# K60.net
KiCad netlist of a schematic drawn in Altium Designer
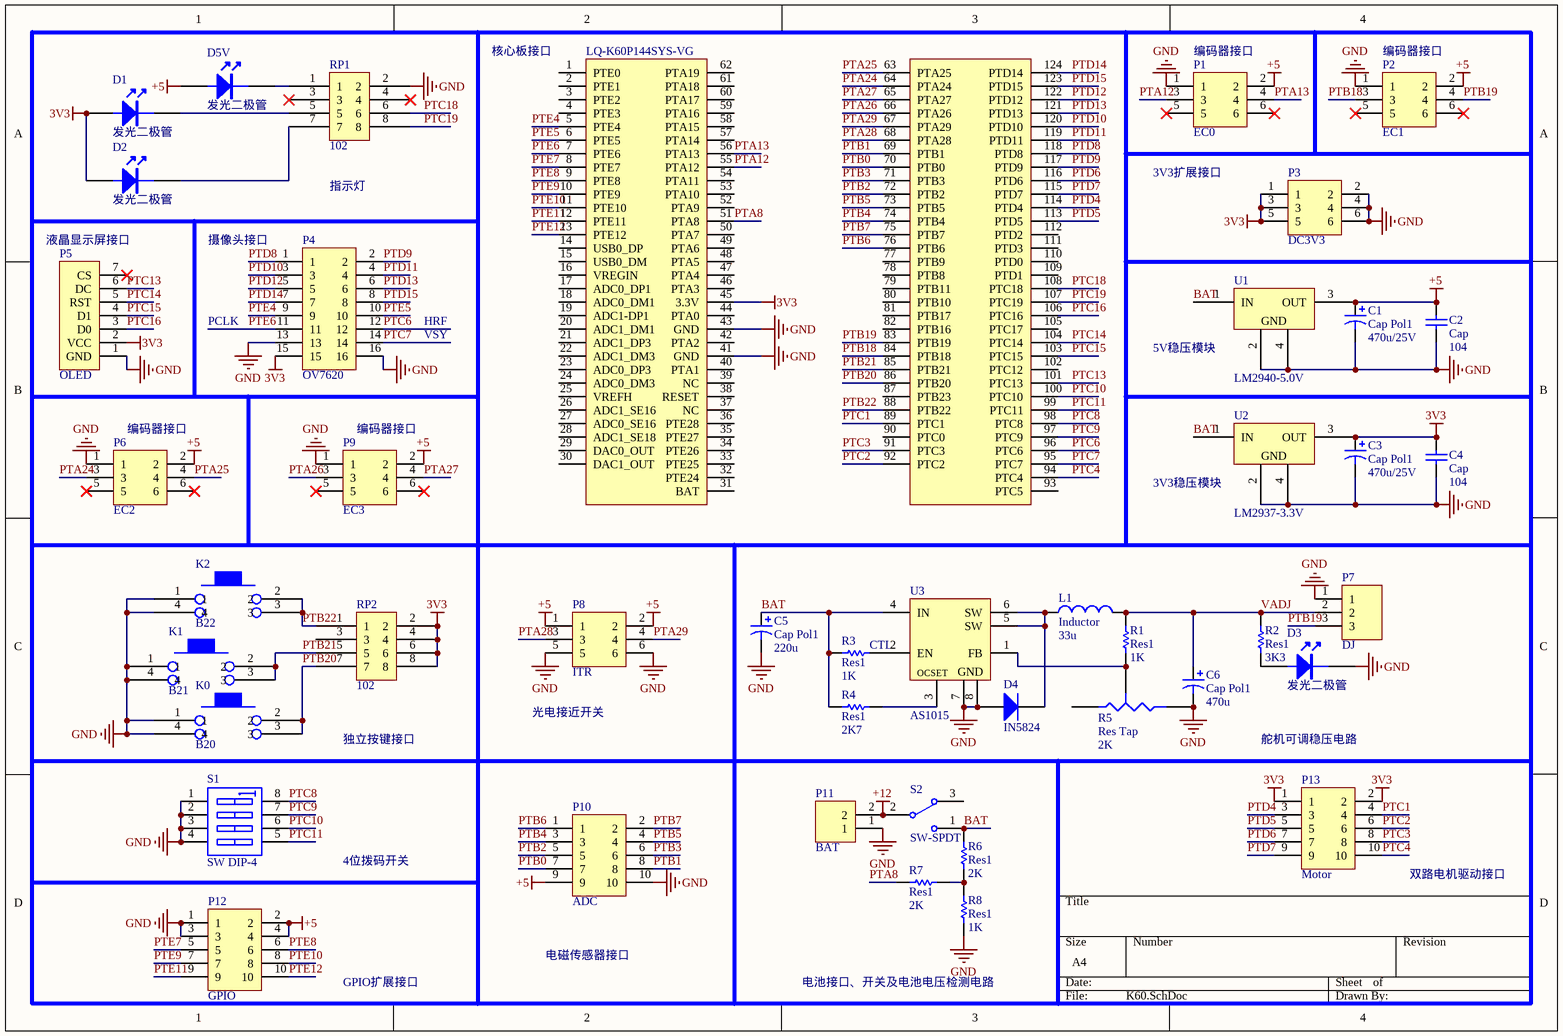
[diagram p0: K60.SchDoc]

(export (version "E")
  (design (tool "Eeschema 10.0.6"))
  (components
    (comp (ref "C1")
      (value "Cap Pol1")
      (footprint "CT 8*7 - C")
      (description "Polarized Capacitor (Radial)")
      (fields (field (name "ALTIUM_VALUE") "470u/25V") (field (name "PUBLISHER") "Altium Limited"))
      (libsource (lib "Miscellaneous Devices") (part "Cap Pol1"))
    )
    (comp (ref "C2")
      (value "Cap")
      (footprint "0603")
      (description "Capacitor")
      (fields (field (name "ALTIUM_VALUE") "104") (field (name "PUBLISHER") "Altium Limited"))
      (libsource (lib "Miscellaneous Devices") (part "Cap"))
    )
    (comp (ref "C3")
      (value "Cap Pol1")
      (footprint "CT 8*7 - C")
      (description "Polarized Capacitor (Radial)")
      (fields (field (name "ALTIUM_VALUE") "470u/25V") (field (name "PUBLISHER") "Altium Limited"))
      (libsource (lib "Miscellaneous Devices") (part "Cap Pol1"))
    )
    (comp (ref "C4")
      (value "Cap")
      (footprint "0603")
      (description "Capacitor")
      (fields (field (name "ALTIUM_VALUE") "104") (field (name "PUBLISHER") "Altium Limited"))
      (libsource (lib "Miscellaneous Devices") (part "Cap"))
    )
    (comp (ref "C5")
      (value "Cap Pol1")
      (footprint "CT 8*7 - C")
      (description "Polarized Capacitor (Radial)")
      (fields (field (name "ALTIUM_VALUE") "220u") (field (name "PUBLISHER") "Altium Limited"))
      (libsource (lib "Miscellaneous Devices") (part "Cap Pol1"))
    )
    (comp (ref "C6")
      (value "Cap Pol1")
      (footprint "CT 8*7 - C")
      (description "Polarized Capacitor (Radial)")
      (fields (field (name "ALTIUM_VALUE") "470u") (field (name "PUBLISHER") "Altium Limited"))
      (libsource (lib "Miscellaneous Devices") (part "Cap Pol1"))
    )
    (comp (ref "D1") (value "发光二极管") (footprint "0603") (libsource (lib "K60") (part "发光二极管")))
    (comp (ref "D2") (value "发光二极管") (footprint "0603") (libsource (lib "K60") (part "发光二极管")))
    (comp (ref "D3") (value "发光二极管") (footprint "0603") (libsource (lib "K60") (part "发光二极管")))
    (comp (ref "D4")
      (value "IN5824")
      (footprint "SMA")
      (description "SS54")
      (fields (field (name "PUBLISHER") "Altium Limited"))
      (libsource (lib "Miscellaneous Devices") (part "Diode"))
    )
    (comp (ref "D5V") (value "发光二极管") (footprint "0603") (libsource (lib "K60") (part "发光二极管")))
    (comp (ref "K0")
      (value "B20")
      (footprint "TSW DIP-6*6*6")
      (libsource (lib "LQ_KXXP144-SYSVGSCH") (part "key"))
    )
    (comp (ref "K1")
      (value "B21")
      (footprint "TSW DIP-6*6*6")
      (libsource (lib "LQ_KXXP144-SYSVGSCH") (part "key"))
    )
    (comp (ref "K2")
      (value "B22")
      (footprint "TSW DIP-6*6*6")
      (libsource (lib "LQ_KXXP144-SYSVGSCH") (part "key"))
    )
    (comp (ref "L1")
      (value "Inductor")
      (footprint "CDRH127")
      (fields (field (name "ALTIUM_VALUE") "33u") (field (name "PUBLISHER") "Altium Limited"))
      (libsource (lib "Miscellaneous Devices") (part "Inductor"))
    )
    (comp (ref "LQ-K60P144SYS-VG")
      (value "~")
      (footprint "LQ_KXXP144-SYSVG")
      (libsource (lib "LQ_KXXP144-SYSVGSCH") (part "LQ_KXXP144-SYSVG"))
    )
    (comp (ref "P1")
      (value "EC0")
      (footprint "2.54排针2X3")
      (description "Header, 3-Pin, Dual row")
      (fields (field (name "PUBLISHER") "Altium Limited"))
      (libsource (lib "Miscellaneous Connectors") (part "Header 3X2"))
    )
    (comp (ref "P2")
      (value "EC1")
      (footprint "2.54排针2X3")
      (description "Header, 3-Pin, Dual row")
      (fields (field (name "PUBLISHER") "Altium Limited"))
      (libsource (lib "Miscellaneous Connectors") (part "Header 3X2"))
    )
    (comp (ref "P3")
      (value "DC3V3")
      (footprint "2.54排针2X3")
      (description "Header, 3-Pin, Dual row")
      (fields (field (name "PUBLISHER") "Altium Limited"))
      (libsource (lib "Miscellaneous Connectors") (part "Header 3X2"))
    )
    (comp (ref "P4")
      (value "OV7620")
      (footprint "2.54排针2X8")
      (description "Header, 8-Pin, Dual row")
      (fields (field (name "PUBLISHER") "Altium Limited"))
      (libsource (lib "Miscellaneous Connectors") (part "Header 8X2"))
    )
    (comp (ref "P5")
      (value "OLED")
      (footprint "HDR1X7")
      (description "Header, 7-Pin")
      (fields (field (name "PUBLISHER") "Altium Limited"))
      (libsource (lib "Miscellaneous Connectors") (part "Header 7"))
    )
    (comp (ref "P6")
      (value "EC2")
      (footprint "2.54排针2X3")
      (description "Header, 3-Pin, Dual row")
      (fields (field (name "PUBLISHER") "Altium Limited"))
      (libsource (lib "Miscellaneous Connectors") (part "Header 3X2"))
    )
    (comp (ref "P7")
      (value "DJ")
      (footprint "2.54排针1X3")
      (description "Header, 3-Pin")
      (fields (field (name "PUBLISHER") "Altium Limited"))
      (libsource (lib "Miscellaneous Connectors") (part "Header 3"))
    )
    (comp (ref "P8")
      (value "ITR")
      (footprint "2.54排针2X3")
      (description "Header, 3-Pin, Dual row")
      (fields (field (name "PUBLISHER") "Altium Limited"))
      (libsource (lib "K60") (part "Header 3X2"))
    )
    (comp (ref "P9")
      (value "EC3")
      (footprint "2.54排针2X3")
      (description "Header, 3-Pin, Dual row")
      (fields (field (name "PUBLISHER") "Altium Limited"))
      (libsource (lib "Miscellaneous Connectors") (part "Header 3X2"))
    )
    (comp (ref "P10")
      (value "ADC")
      (footprint "2.54排针2X5")
      (description "Header, 5-Pin, Dual row")
      (fields (field (name "PUBLISHER") "Altium Limited"))
      (libsource (lib "Miscellaneous Connectors") (part "Header 5X2"))
    )
    (comp (ref "P11")
      (value "BAT")
      (footprint "KF301-2P")
      (description "Header, 2-Pin")
      (fields (field (name "PUBLISHER") "Altium Limited"))
      (libsource (lib "Miscellaneous Connectors") (part "Header 2"))
    )
    (comp (ref "P12")
      (value "GPIO")
      (footprint "2.54排针2X5")
      (description "Header, 5-Pin, Dual row")
      (fields (field (name "PUBLISHER") "Altium Limited"))
      (libsource (lib "Miscellaneous Connectors") (part "Header 5X2"))
    )
    (comp (ref "P13")
      (value "Motor")
      (footprint "2.54排针2X5")
      (description "Header, 5-Pin, Dual row")
      (fields (field (name "PUBLISHER") "Altium Limited"))
      (libsource (lib "K60") (part "Header 5X2"))
    )
    (comp (ref "R1")
      (value "Res1")
      (footprint "0603")
      (description "Resistor")
      (fields (field (name "ALTIUM_VALUE") "1K") (field (name "PUBLISHER") "Altium Limited"))
      (libsource (lib "Miscellaneous Devices") (part "Res1"))
    )
    (comp (ref "R2")
      (value "Res1")
      (footprint "0603")
      (description "Resistor")
      (fields (field (name "ALTIUM_VALUE") "3K3") (field (name "PUBLISHER") "Altium Limited"))
      (libsource (lib "Miscellaneous Devices") (part "Res1"))
    )
    (comp (ref "R3")
      (value "Res1")
      (footprint "0603")
      (description "Resistor")
      (fields (field (name "ALTIUM_VALUE") "1K") (field (name "PUBLISHER") "Altium Limited"))
      (libsource (lib "Miscellaneous Devices") (part "Res1"))
    )
    (comp (ref "R4")
      (value "Res1")
      (footprint "0603")
      (description "Resistor")
      (fields (field (name "ALTIUM_VALUE") "2K7") (field (name "PUBLISHER") "Altium Limited"))
      (libsource (lib "Miscellaneous Devices") (part "Res1"))
    )
    (comp (ref "R5")
      (value "Res Tap")
      (footprint "VR_A1")
      (description "Tapped Resistor")
      (fields (field (name "ALTIUM_VALUE") "2K") (field (name "PUBLISHER") "Altium Limited"))
      (libsource (lib "Miscellaneous Devices") (part "Res Tap"))
    )
    (comp (ref "R6")
      (value "Res1")
      (footprint "0603")
      (description "Resistor")
      (fields (field (name "ALTIUM_VALUE") "2K") (field (name "PUBLISHER") "Altium Limited"))
      (libsource (lib "Miscellaneous Devices") (part "Res1"))
    )
    (comp (ref "R7")
      (value "Res1")
      (footprint "0603")
      (description "Resistor")
      (fields (field (name "ALTIUM_VALUE") "2K") (field (name "PUBLISHER") "Altium Limited"))
      (libsource (lib "Miscellaneous Devices") (part "Res1"))
    )
    (comp (ref "R8")
      (value "Res1")
      (footprint "0603")
      (description "Resistor")
      (fields (field (name "ALTIUM_VALUE") "1K") (field (name "PUBLISHER") "Altium Limited"))
      (libsource (lib "Miscellaneous Devices") (part "Res1"))
    )
    (comp (ref "RP1") (value "102") (footprint "8P4R_0603") (libsource (lib "K60") (part "Res Pak-8")))
    (comp (ref "RP2") (value "102") (footprint "8P4R_0603") (libsource (lib "K60") (part "Res Pak-8")))
    (comp (ref "S1")
      (value "SW DIP-4")
      (footprint "BMKG4")
      (description "DIP Switch, 4 Position, SPST")
      (fields (field (name "PUBLISHER") "Altium Limited"))
      (libsource (lib "Miscellaneous Devices") (part "SW DIP-4"))
    )
    (comp (ref "S2")
      (value "SW-SPDT")
      (footprint "SW3-H2X3_8.6X4.5_L")
      (description "SPDT Subminiature Toggle Switch, Right Angle Mounting, Vertical Actuation")
      (fields (field (name "PUBLISHER") "Altium Limited"))
      (libsource (lib "Miscellaneous Devices") (part "SW-SPDT"))
    )
    (comp (ref "U1")
      (value "LM2940-5.0V")
      (footprint "TO-263-3")
      (description "5V稳压芯片")
      (libsource (lib "Fszhang") (part "LM2940"))
    )
    (comp (ref "U2")
      (value "LM2937-3.3V")
      (footprint "TO-263-3")
      (description "5V稳压芯片")
      (libsource (lib "Fszhang") (part "LM2940"))
    )
    (comp (ref "U3")
      (value "AS1015")
      (footprint "NSO8_N")
      (description "可调升压芯片")
      (libsource (lib "Fszhang") (part "AS1015"))
    )
  )
  (nets
    (net (code "1") (name "+5") (class "Default")
      (node (ref "C1") (pin "1") (pinfunction "1_1") (pintype "passive"))
      (node (ref "C2") (pin "2") (pinfunction "2_2") (pintype "passive"))
      (node (ref "D5V") (pin "1") (pinfunction "A_1") (pintype "passive"))
      (node (ref "P1") (pin "2") (pinfunction "2_2") (pintype "passive"))
      (node (ref "P10") (pin "9") (pinfunction "9_9") (pintype "passive"))
      (node (ref "P12") (pin "2") (pinfunction "2_2") (pintype "passive"))
      (node (ref "P12") (pin "4") (pinfunction "4_4") (pintype "passive"))
      (node (ref "P2") (pin "2") (pinfunction "2_2") (pintype "passive"))
      (node (ref "P6") (pin "2") (pinfunction "2_2") (pintype "passive"))
      (node (ref "P8") (pin "1") (pinfunction "1_1") (pintype "passive"))
      (node (ref "P8") (pin "2") (pinfunction "2_2") (pintype "passive"))
      (node (ref "P9") (pin "2") (pinfunction "2_2") (pintype "passive"))
      (node (ref "U1") (pin "3") (pinfunction "OUT_3") (pintype "power_in"))
    )
    (net (code "2") (name "+12") (class "Default")
      (node (ref "P11") (pin "2") (pinfunction "2_2") (pintype "passive"))
      (node (ref "S2") (pin "2") (pinfunction "2_2") (pintype "passive"))
    )
    (net (code "4") (name "/BAT") (class "Default")
      (node (ref "C5") (pin "1") (pinfunction "1_1") (pintype "passive"))
      (node (ref "R3") (pin "1") (pinfunction "1_1") (pintype "passive"))
      (node (ref "R4") (pin "1") (pinfunction "1_1") (pintype "passive"))
      (node (ref "R6") (pin "2") (pinfunction "2_2") (pintype "passive"))
      (node (ref "S2") (pin "1") (pinfunction "1_1") (pintype "passive"))
      (node (ref "U1") (pin "1") (pinfunction "IN_1") (pintype "power_in"))
      (node (ref "U2") (pin "1") (pinfunction "IN_1") (pintype "power_in"))
      (node (ref "U3") (pin "4") (pinfunction "IN_4") (pintype "power_in"))
    )
    (net (code "5") (name "/PTA8") (class "Default")
      (node (ref "LQ-K60P144SYS-VG") (pin "51") (pinfunction "PTA8_51") (pintype "passive"))
      (node (ref "R7") (pin "1") (pinfunction "1_1") (pintype "passive"))
    )
    (net (code "6") (name "/PTA12") (class "Default")
      (node (ref "LQ-K60P144SYS-VG") (pin "55") (pinfunction "PTA12_55") (pintype "passive"))
      (node (ref "P1") (pin "3") (pinfunction "3_3") (pintype "passive"))
    )
    (net (code "7") (name "/PTA13") (class "Default")
      (node (ref "LQ-K60P144SYS-VG") (pin "56") (pinfunction "PTA13_56") (pintype "passive"))
      (node (ref "P1") (pin "4") (pinfunction "4_4") (pintype "passive"))
    )
    (net (code "8") (name "/PTA24") (class "Default")
      (node (ref "LQ-K60P144SYS-VG") (pin "64") (pinfunction "PTA24_64") (pintype "passive"))
      (node (ref "P6") (pin "3") (pinfunction "3_3") (pintype "passive"))
    )
    (net (code "9") (name "/PTA25") (class "Default")
      (node (ref "LQ-K60P144SYS-VG") (pin "63") (pinfunction "PTA25_63") (pintype "passive"))
      (node (ref "P6") (pin "4") (pinfunction "4_4") (pintype "passive"))
    )
    (net (code "10") (name "/PTA26") (class "Default")
      (node (ref "LQ-K60P144SYS-VG") (pin "66") (pinfunction "PTA26_66") (pintype "passive"))
      (node (ref "P9") (pin "3") (pinfunction "3_3") (pintype "passive"))
    )
    (net (code "11") (name "/PTA27") (class "Default")
      (node (ref "LQ-K60P144SYS-VG") (pin "65") (pinfunction "PTA27_65") (pintype "passive"))
      (node (ref "P9") (pin "4") (pinfunction "4_4") (pintype "passive"))
    )
    (net (code "12") (name "/PTA28") (class "Default")
      (node (ref "LQ-K60P144SYS-VG") (pin "68") (pinfunction "PTA28_68") (pintype "passive"))
      (node (ref "P8") (pin "3") (pinfunction "3_3") (pintype "passive"))
    )
    (net (code "13") (name "/PTA29") (class "Default")
      (node (ref "LQ-K60P144SYS-VG") (pin "67") (pinfunction "PTA29_67") (pintype "passive"))
      (node (ref "P8") (pin "4") (pinfunction "4_4") (pintype "passive"))
    )
    (net (code "14") (name "/PTB0") (class "Default")
      (node (ref "LQ-K60P144SYS-VG") (pin "70") (pinfunction "PTB0_70") (pintype "passive"))
      (node (ref "P10") (pin "7") (pinfunction "7_7") (pintype "passive"))
    )
    (net (code "15") (name "/PTB1") (class "Default")
      (node (ref "LQ-K60P144SYS-VG") (pin "69") (pinfunction "PTB1_69") (pintype "passive"))
      (node (ref "P10") (pin "8") (pinfunction "8_8") (pintype "passive"))
    )
    (net (code "16") (name "/PTB2") (class "Default")
      (node (ref "LQ-K60P144SYS-VG") (pin "72") (pinfunction "PTB2_72") (pintype "passive"))
      (node (ref "P10") (pin "5") (pinfunction "5_5") (pintype "passive"))
    )
    (net (code "17") (name "/PTB3") (class "Default")
      (node (ref "LQ-K60P144SYS-VG") (pin "71") (pinfunction "PTB3_71") (pintype "passive"))
      (node (ref "P10") (pin "6") (pinfunction "6_6") (pintype "passive"))
    )
    (net (code "18") (name "/PTB4") (class "Default")
      (node (ref "LQ-K60P144SYS-VG") (pin "74") (pinfunction "PTB4_74") (pintype "passive"))
      (node (ref "P10") (pin "3") (pinfunction "3_3") (pintype "passive"))
    )
    (net (code "19") (name "/PTB5") (class "Default")
      (node (ref "LQ-K60P144SYS-VG") (pin "73") (pinfunction "PTB5_73") (pintype "passive"))
      (node (ref "P10") (pin "4") (pinfunction "4_4") (pintype "passive"))
    )
    (net (code "20") (name "/PTB6") (class "Default")
      (node (ref "LQ-K60P144SYS-VG") (pin "76") (pinfunction "PTB6_76") (pintype "passive"))
      (node (ref "P10") (pin "1") (pinfunction "1_1") (pintype "passive"))
    )
    (net (code "21") (name "/PTB7") (class "Default")
      (node (ref "LQ-K60P144SYS-VG") (pin "75") (pinfunction "PTB7_75") (pintype "passive"))
      (node (ref "P10") (pin "2") (pinfunction "2_2") (pintype "passive"))
    )
    (net (code "22") (name "/PTB18") (class "Default")
      (node (ref "LQ-K60P144SYS-VG") (pin "84") (pinfunction "PTB18_84") (pintype "passive"))
      (node (ref "P2") (pin "3") (pinfunction "3_3") (pintype "passive"))
    )
    (net (code "23") (name "/PTB19") (class "Default")
      (node (ref "LQ-K60P144SYS-VG") (pin "83") (pinfunction "PTB19_83") (pintype "passive"))
      (node (ref "P2") (pin "4") (pinfunction "4_4") (pintype "passive"))
      (node (ref "P7") (pin "3") (pinfunction "3_3") (pintype "passive"))
    )
    (net (code "24") (name "/PTB20") (class "Default")
      (node (ref "K0") (pin "2") (pinfunction "2_2") (pintype "passive"))
      (node (ref "K0") (pin "3") (pinfunction "3_3") (pintype "passive"))
      (node (ref "LQ-K60P144SYS-VG") (pin "86") (pinfunction "PTB20_86") (pintype "passive"))
      (node (ref "RP2") (pin "7") (pinfunction "7_7") (pintype "passive"))
    )
    (net (code "25") (name "/PTB21") (class "Default")
      (node (ref "K1") (pin "2") (pinfunction "2_2") (pintype "passive"))
      (node (ref "K1") (pin "3") (pinfunction "3_3") (pintype "passive"))
      (node (ref "LQ-K60P144SYS-VG") (pin "85") (pinfunction "PTB21_85") (pintype "passive"))
      (node (ref "RP2") (pin "5") (pinfunction "5_5") (pintype "passive"))
    )
    (net (code "26") (name "/PTB22") (class "Default")
      (node (ref "K2") (pin "2") (pinfunction "2_2") (pintype "passive"))
      (node (ref "K2") (pin "3") (pinfunction "3_3") (pintype "passive"))
      (node (ref "LQ-K60P144SYS-VG") (pin "88") (pinfunction "PTB22_88") (pintype "passive"))
      (node (ref "RP2") (pin "1") (pinfunction "1_1") (pintype "passive"))
    )
    (net (code "27") (name "/PTC1") (class "Default")
      (node (ref "LQ-K60P144SYS-VG") (pin "89") (pinfunction "PTC1_89") (pintype "passive"))
      (node (ref "P13") (pin "4") (pinfunction "4_4") (pintype "passive"))
    )
    (net (code "28") (name "/PTC2") (class "Default")
      (node (ref "LQ-K60P144SYS-VG") (pin "92") (pinfunction "PTC2_92") (pintype "passive"))
      (node (ref "P13") (pin "6") (pinfunction "6_6") (pintype "passive"))
    )
    (net (code "29") (name "/PTC3") (class "Default")
      (node (ref "LQ-K60P144SYS-VG") (pin "91") (pinfunction "PTC3_91") (pintype "passive"))
      (node (ref "P13") (pin "8") (pinfunction "8_8") (pintype "passive"))
    )
    (net (code "30") (name "/PTC4") (class "Default")
      (node (ref "LQ-K60P144SYS-VG") (pin "94") (pinfunction "PTC4_94") (pintype "passive"))
      (node (ref "P13") (pin "10") (pinfunction "10_10") (pintype "passive"))
    )
    (net (code "31") (name "/PTC6") (class "Default")
      (node (ref "LQ-K60P144SYS-VG") (pin "96") (pinfunction "PTC6_96") (pintype "passive"))
      (node (ref "P4") (pin "12") (pinfunction "12_12") (pintype "passive"))
    )
    (net (code "32") (name "/PTC7") (class "Default")
      (node (ref "LQ-K60P144SYS-VG") (pin "95") (pinfunction "PTC7_95") (pintype "passive"))
      (node (ref "P4") (pin "14") (pinfunction "14_14") (pintype "passive"))
    )
    (net (code "33") (name "/PTC8") (class "Default")
      (node (ref "LQ-K60P144SYS-VG") (pin "98") (pinfunction "PTC8_98") (pintype "passive"))
      (node (ref "S1") (pin "8") (pinfunction "B1_8") (pintype "passive"))
    )
    (net (code "34") (name "/PTC9") (class "Default")
      (node (ref "LQ-K60P144SYS-VG") (pin "97") (pinfunction "PTC9_97") (pintype "passive"))
      (node (ref "S1") (pin "7") (pinfunction "B2_7") (pintype "passive"))
    )
    (net (code "35") (name "/PTC10") (class "Default")
      (node (ref "LQ-K60P144SYS-VG") (pin "100") (pinfunction "PTC10_100") (pintype "passive"))
      (node (ref "S1") (pin "6") (pinfunction "B3_6") (pintype "passive"))
    )
    (net (code "36") (name "/PTC11") (class "Default")
      (node (ref "LQ-K60P144SYS-VG") (pin "99") (pinfunction "PTC11_99") (pintype "passive"))
      (node (ref "S1") (pin "5") (pinfunction "B4_5") (pintype "passive"))
    )
    (net (code "37") (name "/PTC13") (class "Default")
      (node (ref "LQ-K60P144SYS-VG") (pin "101") (pinfunction "PTC13_101") (pintype "passive"))
      (node (ref "P5") (pin "6") (pinfunction "DC_6") (pintype "passive"))
    )
    (net (code "38") (name "/PTC14") (class "Default")
      (node (ref "LQ-K60P144SYS-VG") (pin "104") (pinfunction "PTC14_104") (pintype "passive"))
      (node (ref "P5") (pin "5") (pinfunction "RST_5") (pintype "passive"))
    )
    (net (code "39") (name "/PTC15") (class "Default")
      (node (ref "LQ-K60P144SYS-VG") (pin "103") (pinfunction "PTC15_103") (pintype "passive"))
      (node (ref "P5") (pin "4") (pinfunction "D1_4") (pintype "passive"))
    )
    (net (code "40") (name "/PTC16") (class "Default")
      (node (ref "LQ-K60P144SYS-VG") (pin "106") (pinfunction "PTC16_106") (pintype "passive"))
      (node (ref "P5") (pin "3") (pinfunction "D0_3") (pintype "passive"))
    )
    (net (code "41") (name "/PTC18") (class "Default")
      (node (ref "LQ-K60P144SYS-VG") (pin "108") (pinfunction "PTC18_108") (pintype "passive"))
      (node (ref "RP1") (pin "6") (pinfunction "6_6") (pintype "passive"))
    )
    (net (code "42") (name "/PTC19") (class "Default")
      (node (ref "LQ-K60P144SYS-VG") (pin "107") (pinfunction "PTC19_107") (pintype "passive"))
      (node (ref "RP1") (pin "8") (pinfunction "8_8") (pintype "passive"))
    )
    (net (code "43") (name "/PTD4") (class "Default")
      (node (ref "LQ-K60P144SYS-VG") (pin "114") (pinfunction "PTD4_114") (pintype "passive"))
      (node (ref "P13") (pin "3") (pinfunction "3_3") (pintype "passive"))
    )
    (net (code "44") (name "/PTD5") (class "Default")
      (node (ref "LQ-K60P144SYS-VG") (pin "113") (pinfunction "PTD5_113") (pintype "passive"))
      (node (ref "P13") (pin "5") (pinfunction "5_5") (pintype "passive"))
    )
    (net (code "45") (name "/PTD6") (class "Default")
      (node (ref "LQ-K60P144SYS-VG") (pin "116") (pinfunction "PTD6_116") (pintype "passive"))
      (node (ref "P13") (pin "7") (pinfunction "7_7") (pintype "passive"))
    )
    (net (code "46") (name "/PTD7") (class "Default")
      (node (ref "LQ-K60P144SYS-VG") (pin "115") (pinfunction "PTD7_115") (pintype "passive"))
      (node (ref "P13") (pin "9") (pinfunction "9_9") (pintype "passive"))
    )
    (net (code "47") (name "/PTD8") (class "Default")
      (node (ref "LQ-K60P144SYS-VG") (pin "118") (pinfunction "PTD8_118") (pintype "passive"))
      (node (ref "P4") (pin "1") (pinfunction "1_1") (pintype "passive"))
    )
    (net (code "48") (name "/PTD9") (class "Default")
      (node (ref "LQ-K60P144SYS-VG") (pin "117") (pinfunction "PTD9_117") (pintype "passive"))
      (node (ref "P4") (pin "2") (pinfunction "2_2") (pintype "passive"))
    )
    (net (code "49") (name "/PTD10") (class "Default")
      (node (ref "LQ-K60P144SYS-VG") (pin "120") (pinfunction "PTD10_120") (pintype "passive"))
      (node (ref "P4") (pin "3") (pinfunction "3_3") (pintype "passive"))
    )
    (net (code "50") (name "/PTD11") (class "Default")
      (node (ref "LQ-K60P144SYS-VG") (pin "119") (pinfunction "PTD11_119") (pintype "passive"))
      (node (ref "P4") (pin "4") (pinfunction "4_4") (pintype "passive"))
    )
    (net (code "51") (name "/PTD12") (class "Default")
      (node (ref "LQ-K60P144SYS-VG") (pin "122") (pinfunction "PTD12_122") (pintype "passive"))
      (node (ref "P4") (pin "5") (pinfunction "5_5") (pintype "passive"))
    )
    (net (code "52") (name "/PTD13") (class "Default")
      (node (ref "LQ-K60P144SYS-VG") (pin "121") (pinfunction "PTD13_121") (pintype "passive"))
      (node (ref "P4") (pin "6") (pinfunction "6_6") (pintype "passive"))
    )
    (net (code "53") (name "/PTD14") (class "Default")
      (node (ref "LQ-K60P144SYS-VG") (pin "124") (pinfunction "PTD14_124") (pintype "passive"))
      (node (ref "P4") (pin "7") (pinfunction "7_7") (pintype "passive"))
    )
    (net (code "54") (name "/PTD15") (class "Default")
      (node (ref "LQ-K60P144SYS-VG") (pin "123") (pinfunction "PTD15_123") (pintype "passive"))
      (node (ref "P4") (pin "8") (pinfunction "8_8") (pintype "passive"))
    )
    (net (code "55") (name "/PTE4") (class "Default")
      (node (ref "LQ-K60P144SYS-VG") (pin "5") (pinfunction "PTE4_5") (pintype "passive"))
      (node (ref "P4") (pin "9") (pinfunction "9_9") (pintype "passive"))
    )
    (net (code "56") (name "/PTE5") (class "Default")
      (node (ref "LQ-K60P144SYS-VG") (pin "6") (pinfunction "PTE5_6") (pintype "passive"))
      (node (ref "P4") (pin "10") (pinfunction "10_10") (pintype "passive"))
    )
    (net (code "57") (name "/PTE6") (class "Default")
      (node (ref "LQ-K60P144SYS-VG") (pin "7") (pinfunction "PTE6_7") (pintype "passive"))
      (node (ref "P4") (pin "11") (pinfunction "11_11") (pintype "passive"))
    )
    (net (code "58") (name "/PTE7") (class "Default")
      (node (ref "LQ-K60P144SYS-VG") (pin "8") (pinfunction "PTE7_8") (pintype "passive"))
      (node (ref "P12") (pin "5") (pinfunction "5_5") (pintype "passive"))
    )
    (net (code "59") (name "/PTE8") (class "Default")
      (node (ref "LQ-K60P144SYS-VG") (pin "9") (pinfunction "PTE8_9") (pintype "passive"))
      (node (ref "P12") (pin "6") (pinfunction "6_6") (pintype "passive"))
    )
    (net (code "60") (name "/PTE9") (class "Default")
      (node (ref "LQ-K60P144SYS-VG") (pin "10") (pinfunction "PTE9_10") (pintype "passive"))
      (node (ref "P12") (pin "7") (pinfunction "7_7") (pintype "passive"))
    )
    (net (code "61") (name "/PTE10") (class "Default")
      (node (ref "LQ-K60P144SYS-VG") (pin "11") (pinfunction "PTE10_11") (pintype "passive"))
      (node (ref "P12") (pin "8") (pinfunction "8_8") (pintype "passive"))
    )
    (net (code "62") (name "/PTE11") (class "Default")
      (node (ref "LQ-K60P144SYS-VG") (pin "12") (pinfunction "PTE11_12") (pintype "passive"))
      (node (ref "P12") (pin "9") (pinfunction "9_9") (pintype "passive"))
    )
    (net (code "63") (name "/PTE12") (class "Default")
      (node (ref "LQ-K60P144SYS-VG") (pin "13") (pinfunction "PTE12_13") (pintype "passive"))
      (node (ref "P12") (pin "10") (pinfunction "10_10") (pintype "passive"))
    )
    (net (code "64") (name "/VADJ") (class "Default")
      (node (ref "C6") (pin "1") (pinfunction "1_1") (pintype "passive"))
      (node (ref "L1") (pin "2") (pinfunction "2_2") (pintype "passive"))
      (node (ref "P7") (pin "2") (pinfunction "2_2") (pintype "passive"))
      (node (ref "R1") (pin "2") (pinfunction "2_2") (pintype "passive"))
      (node (ref "R2") (pin "2") (pinfunction "2_2") (pintype "passive"))
    )
    (net (code "65") (name "3V3") (class "Default")
      (node (ref "C3") (pin "1") (pinfunction "1_1") (pintype "passive"))
      (node (ref "C4") (pin "2") (pinfunction "2_2") (pintype "passive"))
      (node (ref "D1") (pin "1") (pinfunction "A_1") (pintype "passive"))
      (node (ref "D2") (pin "1") (pinfunction "A_1") (pintype "passive"))
      (node (ref "LQ-K60P144SYS-VG") (pin "45") (pinfunction "3.3V_45") (pintype "passive"))
      (node (ref "P13") (pin "1") (pinfunction "1_1") (pintype "passive"))
      (node (ref "P13") (pin "2") (pinfunction "2_2") (pintype "passive"))
      (node (ref "P3") (pin "1") (pinfunction "1_1") (pintype "passive"))
      (node (ref "P3") (pin "3") (pinfunction "3_3") (pintype "passive"))
      (node (ref "P3") (pin "5") (pinfunction "5_5") (pintype "passive"))
      (node (ref "P4") (pin "15") (pinfunction "15_15") (pintype "passive"))
      (node (ref "P5") (pin "2") (pinfunction "VCC_2") (pintype "passive"))
      (node (ref "RP2") (pin "2") (pinfunction "2_2") (pintype "passive"))
      (node (ref "RP2") (pin "4") (pinfunction "4_4") (pintype "passive"))
      (node (ref "RP2") (pin "6") (pinfunction "6_6") (pintype "passive"))
      (node (ref "RP2") (pin "8") (pinfunction "8_8") (pintype "passive"))
      (node (ref "U2") (pin "3") (pinfunction "OUT_3") (pintype "power_in"))
    )
    (net (code "66") (name "GND") (class "Default")
      (node (ref "C1") (pin "2") (pinfunction "2_2") (pintype "passive"))
      (node (ref "C2") (pin "1") (pinfunction "1_1") (pintype "passive"))
      (node (ref "C3") (pin "2") (pinfunction "2_2") (pintype "passive"))
      (node (ref "C4") (pin "1") (pinfunction "1_1") (pintype "passive"))
      (node (ref "C5") (pin "2") (pinfunction "2_2") (pintype "passive"))
      (node (ref "C6") (pin "2") (pinfunction "2_2") (pintype "passive"))
      (node (ref "D3") (pin "2") (pinfunction "K_2") (pintype "passive"))
      (node (ref "D4") (pin "1") (pinfunction "A_1") (pintype "passive"))
      (node (ref "K0") (pin "1") (pinfunction "1_1") (pintype "passive"))
      (node (ref "K0") (pin "4") (pinfunction "4_4") (pintype "passive"))
      (node (ref "K1") (pin "1") (pinfunction "1_1") (pintype "passive"))
      (node (ref "K1") (pin "4") (pinfunction "4_4") (pintype "passive"))
      (node (ref "K2") (pin "1") (pinfunction "1_1") (pintype "passive"))
      (node (ref "K2") (pin "4") (pinfunction "4_4") (pintype "passive"))
      (node (ref "LQ-K60P144SYS-VG") (pin "41") (pinfunction "GND_41") (pintype "passive"))
      (node (ref "LQ-K60P144SYS-VG") (pin "43") (pinfunction "GND_43") (pintype "passive"))
      (node (ref "P1") (pin "1") (pinfunction "1_1") (pintype "passive"))
      (node (ref "P10") (pin "10") (pinfunction "10_10") (pintype "passive"))
      (node (ref "P11") (pin "1") (pinfunction "1_1") (pintype "passive"))
      (node (ref "P12") (pin "1") (pinfunction "1_1") (pintype "passive"))
      (node (ref "P12") (pin "3") (pinfunction "3_3") (pintype "passive"))
      (node (ref "P2") (pin "1") (pinfunction "1_1") (pintype "passive"))
      (node (ref "P3") (pin "2") (pinfunction "2_2") (pintype "passive"))
      (node (ref "P3") (pin "4") (pinfunction "4_4") (pintype "passive"))
      (node (ref "P3") (pin "6") (pinfunction "6_6") (pintype "passive"))
      (node (ref "P4") (pin "13") (pinfunction "13_13") (pintype "passive"))
      (node (ref "P4") (pin "16") (pinfunction "16_16") (pintype "passive"))
      (node (ref "P5") (pin "1") (pinfunction "GND_1") (pintype "passive"))
      (node (ref "P6") (pin "1") (pinfunction "1_1") (pintype "passive"))
      (node (ref "P7") (pin "1") (pinfunction "1_1") (pintype "passive"))
      (node (ref "P8") (pin "5") (pinfunction "5_5") (pintype "passive"))
      (node (ref "P8") (pin "6") (pinfunction "6_6") (pintype "passive"))
      (node (ref "P9") (pin "1") (pinfunction "1_1") (pintype "passive"))
      (node (ref "R5") (pin "2") (pinfunction "B_2") (pintype "passive"))
      (node (ref "R8") (pin "1") (pinfunction "1_1") (pintype "passive"))
      (node (ref "RP1") (pin "2") (pinfunction "2_2") (pintype "passive"))
      (node (ref "S1") (pin "1") (pinfunction "A1_1") (pintype "passive"))
      (node (ref "S1") (pin "2") (pinfunction "A2_2") (pintype "passive"))
      (node (ref "S1") (pin "3") (pinfunction "A3_3") (pintype "passive"))
      (node (ref "S1") (pin "4") (pinfunction "A4_4") (pintype "passive"))
      (node (ref "U1") (pin "2") (pinfunction "GND_2") (pintype "power_in"))
      (node (ref "U1") (pin "4") (pinfunction "GND_4") (pintype "power_in"))
      (node (ref "U2") (pin "2") (pinfunction "GND_2") (pintype "power_in"))
      (node (ref "U2") (pin "4") (pinfunction "GND_4") (pintype "power_in"))
      (node (ref "U3") (pin "7") (pinfunction "GND_7") (pintype "power_in"))
      (node (ref "U3") (pin "8") (pinfunction "GND_8") (pintype "power_in"))
    )
    (net (code "67") (name "Net-(D1-K)") (class "Default")
      (node (ref "D1") (pin "2") (pinfunction "K_2") (pintype "passive"))
      (node (ref "RP1") (pin "5") (pinfunction "5_5") (pintype "passive"))
    )
    (net (code "68") (name "Net-(D2-K)") (class "Default")
      (node (ref "D2") (pin "2") (pinfunction "K_2") (pintype "passive"))
      (node (ref "RP1") (pin "7") (pinfunction "7_7") (pintype "passive"))
    )
    (net (code "69") (name "Net-(D3-A)") (class "Default")
      (node (ref "D3") (pin "1") (pinfunction "A_1") (pintype "passive"))
      (node (ref "R2") (pin "1") (pinfunction "1_1") (pintype "passive"))
    )
    (net (code "70") (name "Net-(D4-K)") (class "Default")
      (node (ref "D4") (pin "2") (pinfunction "K_2") (pintype "passive"))
      (node (ref "L1") (pin "1") (pinfunction "1_1") (pintype "passive"))
      (node (ref "U3") (pin "5") (pinfunction "SW_5") (pintype "power_in"))
      (node (ref "U3") (pin "6") (pinfunction "SW_6") (pintype "power_in"))
    )
    (net (code "71") (name "Net-(D5V-K)") (class "Default")
      (node (ref "D5V") (pin "2") (pinfunction "K_2") (pintype "passive"))
      (node (ref "RP1") (pin "1") (pinfunction "1_1") (pintype "passive"))
    )
    (net (code "72") (name "Net-(R5-TAP)") (class "Default")
      (node (ref "R1") (pin "1") (pinfunction "1_1") (pintype "passive"))
      (node (ref "R5") (pin "3") (pinfunction "TAP_3") (pintype "passive"))
      (node (ref "U3") (pin "1") (pinfunction "FB_1") (pintype "power_in"))
    )
    (net (code "73") (name "Net-(R6-Pad1)") (class "Default")
      (node (ref "R6") (pin "1") (pinfunction "1_1") (pintype "passive"))
      (node (ref "R7") (pin "2") (pinfunction "2_2") (pintype "passive"))
      (node (ref "R8") (pin "2") (pinfunction "2_2") (pintype "passive"))
    )
    (net (code "74") (name "Net-(U3-EN)") (class "Default")
      (node (ref "R3") (pin "2") (pinfunction "2_2") (pintype "passive"))
      (node (ref "U3") (pin "2") (pinfunction "EN_2") (pintype "power_in"))
    )
    (net (code "75") (name "Net-(U3-OCSET)") (class "Default")
      (node (ref "R4") (pin "2") (pinfunction "2_2") (pintype "passive"))
      (node (ref "U3") (pin "3") (pinfunction "OCSET_3") (pintype "power_in"))
    )
    (net (code "76") (name "unconnected-(LQ-K60P144SYS-VG-ADC0_DM1-Pad18)") (class "Default")
      (node (ref "LQ-K60P144SYS-VG") (pin "18") (pinfunction "ADC0_DM1_18") (pintype "passive"))
    )
    (net (code "77") (name "unconnected-(LQ-K60P144SYS-VG-ADC0_DM3-Pad24)") (class "Default")
      (node (ref "LQ-K60P144SYS-VG") (pin "24") (pinfunction "ADC0_DM3_24") (pintype "passive"))
    )
    (net (code "78") (name "unconnected-(LQ-K60P144SYS-VG-ADC0_DP1-Pad17)") (class "Default")
      (node (ref "LQ-K60P144SYS-VG") (pin "17") (pinfunction "ADC0_DP1_17") (pintype "passive"))
    )
    (net (code "79") (name "unconnected-(LQ-K60P144SYS-VG-ADC0_DP3-Pad23)") (class "Default")
      (node (ref "LQ-K60P144SYS-VG") (pin "23") (pinfunction "ADC0_DP3_23") (pintype "passive"))
    )
    (net (code "80") (name "unconnected-(LQ-K60P144SYS-VG-ADC0_SE16-Pad27)") (class "Default")
      (node (ref "LQ-K60P144SYS-VG") (pin "27") (pinfunction "ADC0_SE16_27") (pintype "passive"))
    )
    (net (code "81") (name "unconnected-(LQ-K60P144SYS-VG-ADC1-DP1-Pad19)") (class "Default")
      (node (ref "LQ-K60P144SYS-VG") (pin "19") (pinfunction "ADC1-DP1_19") (pintype "passive"))
    )
    (net (code "82") (name "unconnected-(LQ-K60P144SYS-VG-ADC1_DM1-Pad20)") (class "Default")
      (node (ref "LQ-K60P144SYS-VG") (pin "20") (pinfunction "ADC1_DM1_20") (pintype "passive"))
    )
    (net (code "83") (name "unconnected-(LQ-K60P144SYS-VG-ADC1_DM3-Pad22)") (class "Default")
      (node (ref "LQ-K60P144SYS-VG") (pin "22") (pinfunction "ADC1_DM3_22") (pintype "passive"))
    )
    (net (code "84") (name "unconnected-(LQ-K60P144SYS-VG-ADC1_DP3-Pad21)") (class "Default")
      (node (ref "LQ-K60P144SYS-VG") (pin "21") (pinfunction "ADC1_DP3_21") (pintype "passive"))
    )
    (net (code "85") (name "unconnected-(LQ-K60P144SYS-VG-ADC1_SE16-Pad26)") (class "Default")
      (node (ref "LQ-K60P144SYS-VG") (pin "26") (pinfunction "ADC1_SE16_26") (pintype "passive"))
    )
    (net (code "86") (name "unconnected-(LQ-K60P144SYS-VG-ADC1_SE18-Pad28)") (class "Default")
      (node (ref "LQ-K60P144SYS-VG") (pin "28") (pinfunction "ADC1_SE18_28") (pintype "passive"))
    )
    (net (code "87") (name "unconnected-(LQ-K60P144SYS-VG-BAT-Pad31)") (class "Default")
      (node (ref "LQ-K60P144SYS-VG") (pin "31") (pinfunction "BAT_31") (pintype "passive"))
    )
    (net (code "88") (name "unconnected-(LQ-K60P144SYS-VG-DAC0_OUT-Pad29)") (class "Default")
      (node (ref "LQ-K60P144SYS-VG") (pin "29") (pinfunction "DAC0_OUT_29") (pintype "passive"))
    )
    (net (code "89") (name "unconnected-(LQ-K60P144SYS-VG-DAC1_OUT-Pad30)") (class "Default")
      (node (ref "LQ-K60P144SYS-VG") (pin "30") (pinfunction "DAC1_OUT_30") (pintype "passive"))
    )
    (net (code "90") (name "unconnected-(LQ-K60P144SYS-VG-NC-Pad37)") (class "Default")
      (node (ref "LQ-K60P144SYS-VG") (pin "37") (pinfunction "NC_37") (pintype "passive"))
    )
    (net (code "91") (name "unconnected-(LQ-K60P144SYS-VG-NC-Pad39)") (class "Default")
      (node (ref "LQ-K60P144SYS-VG") (pin "39") (pinfunction "NC_39") (pintype "passive"))
    )
    (net (code "92") (name "unconnected-(LQ-K60P144SYS-VG-PTA0-Pad44)") (class "Default")
      (node (ref "LQ-K60P144SYS-VG") (pin "44") (pinfunction "PTA0_44") (pintype "passive"))
    )
    (net (code "93") (name "unconnected-(LQ-K60P144SYS-VG-PTA1-Pad40)") (class "Default")
      (node (ref "LQ-K60P144SYS-VG") (pin "40") (pinfunction "PTA1_40") (pintype "passive"))
    )
    (net (code "94") (name "unconnected-(LQ-K60P144SYS-VG-PTA2-Pad42)") (class "Default")
      (node (ref "LQ-K60P144SYS-VG") (pin "42") (pinfunction "PTA2_42") (pintype "passive"))
    )
    (net (code "95") (name "unconnected-(LQ-K60P144SYS-VG-PTA3-Pad46)") (class "Default")
      (node (ref "LQ-K60P144SYS-VG") (pin "46") (pinfunction "PTA3_46") (pintype "passive"))
    )
    (net (code "96") (name "unconnected-(LQ-K60P144SYS-VG-PTA4-Pad47)") (class "Default")
      (node (ref "LQ-K60P144SYS-VG") (pin "47") (pinfunction "PTA4_47") (pintype "passive"))
    )
    (net (code "97") (name "unconnected-(LQ-K60P144SYS-VG-PTA5-Pad48)") (class "Default")
      (node (ref "LQ-K60P144SYS-VG") (pin "48") (pinfunction "PTA5_48") (pintype "passive"))
    )
    (net (code "98") (name "unconnected-(LQ-K60P144SYS-VG-PTA6-Pad49)") (class "Default")
      (node (ref "LQ-K60P144SYS-VG") (pin "49") (pinfunction "PTA6_49") (pintype "passive"))
    )
    (net (code "99") (name "unconnected-(LQ-K60P144SYS-VG-PTA7-Pad50)") (class "Default")
      (node (ref "LQ-K60P144SYS-VG") (pin "50") (pinfunction "PTA7_50") (pintype "passive"))
    )
    (net (code "100") (name "unconnected-(LQ-K60P144SYS-VG-PTA9-Pad52)") (class "Default")
      (node (ref "LQ-K60P144SYS-VG") (pin "52") (pinfunction "PTA9_52") (pintype "passive"))
    )
    (net (code "101") (name "unconnected-(LQ-K60P144SYS-VG-PTA10-Pad53)") (class "Default")
      (node (ref "LQ-K60P144SYS-VG") (pin "53") (pinfunction "PTA10_53") (pintype "passive"))
    )
    (net (code "102") (name "unconnected-(LQ-K60P144SYS-VG-PTA11-Pad54)") (class "Default")
      (node (ref "LQ-K60P144SYS-VG") (pin "54") (pinfunction "PTA11_54") (pintype "passive"))
    )
    (net (code "103") (name "unconnected-(LQ-K60P144SYS-VG-PTA14-Pad57)") (class "Default")
      (node (ref "LQ-K60P144SYS-VG") (pin "57") (pinfunction "PTA14_57") (pintype "passive"))
    )
    (net (code "104") (name "unconnected-(LQ-K60P144SYS-VG-PTA15-Pad58)") (class "Default")
      (node (ref "LQ-K60P144SYS-VG") (pin "58") (pinfunction "PTA15_58") (pintype "passive"))
    )
    (net (code "105") (name "unconnected-(LQ-K60P144SYS-VG-PTA16-Pad59)") (class "Default")
      (node (ref "LQ-K60P144SYS-VG") (pin "59") (pinfunction "PTA16_59") (pintype "passive"))
    )
    (net (code "106") (name "unconnected-(LQ-K60P144SYS-VG-PTA17-Pad60)") (class "Default")
      (node (ref "LQ-K60P144SYS-VG") (pin "60") (pinfunction "PTA17_60") (pintype "passive"))
    )
    (net (code "107") (name "unconnected-(LQ-K60P144SYS-VG-PTA18-Pad61)") (class "Default")
      (node (ref "LQ-K60P144SYS-VG") (pin "61") (pinfunction "PTA18_61") (pintype "passive"))
    )
    (net (code "108") (name "unconnected-(LQ-K60P144SYS-VG-PTA19-Pad62)") (class "Default")
      (node (ref "LQ-K60P144SYS-VG") (pin "62") (pinfunction "PTA19_62") (pintype "passive"))
    )
    (net (code "109") (name "unconnected-(LQ-K60P144SYS-VG-PTB8-Pad78)") (class "Default")
      (node (ref "LQ-K60P144SYS-VG") (pin "78") (pinfunction "PTB8_78") (pintype "passive"))
    )
    (net (code "110") (name "unconnected-(LQ-K60P144SYS-VG-PTB9-Pad77)") (class "Default")
      (node (ref "LQ-K60P144SYS-VG") (pin "77") (pinfunction "PTB9_77") (pintype "passive"))
    )
    (net (code "111") (name "unconnected-(LQ-K60P144SYS-VG-PTB10-Pad80)") (class "Default")
      (node (ref "LQ-K60P144SYS-VG") (pin "80") (pinfunction "PTB10_80") (pintype "passive"))
    )
    (net (code "112") (name "unconnected-(LQ-K60P144SYS-VG-PTB11-Pad79)") (class "Default")
      (node (ref "LQ-K60P144SYS-VG") (pin "79") (pinfunction "PTB11_79") (pintype "passive"))
    )
    (net (code "113") (name "unconnected-(LQ-K60P144SYS-VG-PTB16-Pad82)") (class "Default")
      (node (ref "LQ-K60P144SYS-VG") (pin "82") (pinfunction "PTB16_82") (pintype "passive"))
    )
    (net (code "114") (name "unconnected-(LQ-K60P144SYS-VG-PTB17-Pad81)") (class "Default")
      (node (ref "LQ-K60P144SYS-VG") (pin "81") (pinfunction "PTB17_81") (pintype "passive"))
    )
    (net (code "115") (name "unconnected-(LQ-K60P144SYS-VG-PTB23-Pad87)") (class "Default")
      (node (ref "LQ-K60P144SYS-VG") (pin "87") (pinfunction "PTB23_87") (pintype "passive"))
    )
    (net (code "116") (name "unconnected-(LQ-K60P144SYS-VG-PTC0-Pad90)") (class "Default")
      (node (ref "LQ-K60P144SYS-VG") (pin "90") (pinfunction "PTC0_90") (pintype "passive"))
    )
    (net (code "117") (name "unconnected-(LQ-K60P144SYS-VG-PTC5-Pad93)") (class "Default")
      (node (ref "LQ-K60P144SYS-VG") (pin "93") (pinfunction "PTC5_93") (pintype "passive"))
    )
    (net (code "118") (name "unconnected-(LQ-K60P144SYS-VG-PTC12-Pad102)") (class "Default")
      (node (ref "LQ-K60P144SYS-VG") (pin "102") (pinfunction "PTC12_102") (pintype "passive"))
    )
    (net (code "119") (name "unconnected-(LQ-K60P144SYS-VG-PTC17-Pad105)") (class "Default")
      (node (ref "LQ-K60P144SYS-VG") (pin "105") (pinfunction "PTC17_105") (pintype "passive"))
    )
    (net (code "120") (name "unconnected-(LQ-K60P144SYS-VG-PTD0-Pad110)") (class "Default")
      (node (ref "LQ-K60P144SYS-VG") (pin "110") (pinfunction "PTD0_110") (pintype "passive"))
    )
    (net (code "121") (name "unconnected-(LQ-K60P144SYS-VG-PTD1-Pad109)") (class "Default")
      (node (ref "LQ-K60P144SYS-VG") (pin "109") (pinfunction "PTD1_109") (pintype "passive"))
    )
    (net (code "122") (name "unconnected-(LQ-K60P144SYS-VG-PTD2-Pad112)") (class "Default")
      (node (ref "LQ-K60P144SYS-VG") (pin "112") (pinfunction "PTD2_112") (pintype "passive"))
    )
    (net (code "123") (name "unconnected-(LQ-K60P144SYS-VG-PTD3-Pad111)") (class "Default")
      (node (ref "LQ-K60P144SYS-VG") (pin "111") (pinfunction "PTD3_111") (pintype "passive"))
    )
    (net (code "124") (name "unconnected-(LQ-K60P144SYS-VG-PTE0-Pad1)") (class "Default")
      (node (ref "LQ-K60P144SYS-VG") (pin "1") (pinfunction "PTE0_1") (pintype "passive"))
    )
    (net (code "125") (name "unconnected-(LQ-K60P144SYS-VG-PTE1-Pad2)") (class "Default")
      (node (ref "LQ-K60P144SYS-VG") (pin "2") (pinfunction "PTE1_2") (pintype "passive"))
    )
    (net (code "126") (name "unconnected-(LQ-K60P144SYS-VG-PTE2-Pad3)") (class "Default")
      (node (ref "LQ-K60P144SYS-VG") (pin "3") (pinfunction "PTE2_3") (pintype "passive"))
    )
    (net (code "127") (name "unconnected-(LQ-K60P144SYS-VG-PTE3-Pad4)") (class "Default")
      (node (ref "LQ-K60P144SYS-VG") (pin "4") (pinfunction "PTE3_4") (pintype "passive"))
    )
    (net (code "128") (name "unconnected-(LQ-K60P144SYS-VG-PTE24-Pad32)") (class "Default")
      (node (ref "LQ-K60P144SYS-VG") (pin "32") (pinfunction "PTE24_32") (pintype "passive"))
    )
    (net (code "129") (name "unconnected-(LQ-K60P144SYS-VG-PTE25-Pad33)") (class "Default")
      (node (ref "LQ-K60P144SYS-VG") (pin "33") (pinfunction "PTE25_33") (pintype "passive"))
    )
    (net (code "130") (name "unconnected-(LQ-K60P144SYS-VG-PTE26-Pad34)") (class "Default")
      (node (ref "LQ-K60P144SYS-VG") (pin "34") (pinfunction "PTE26_34") (pintype "passive"))
    )
    (net (code "131") (name "unconnected-(LQ-K60P144SYS-VG-PTE27-Pad35)") (class "Default")
      (node (ref "LQ-K60P144SYS-VG") (pin "35") (pinfunction "PTE27_35") (pintype "passive"))
    )
    (net (code "132") (name "unconnected-(LQ-K60P144SYS-VG-PTE28-Pad36)") (class "Default")
      (node (ref "LQ-K60P144SYS-VG") (pin "36") (pinfunction "PTE28_36") (pintype "passive"))
    )
    (net (code "133") (name "unconnected-(LQ-K60P144SYS-VG-RESET-Pad38)") (class "Default")
      (node (ref "LQ-K60P144SYS-VG") (pin "38") (pinfunction "RESET_38") (pintype "passive"))
    )
    (net (code "134") (name "unconnected-(LQ-K60P144SYS-VG-USB0_DM-Pad15)") (class "Default")
      (node (ref "LQ-K60P144SYS-VG") (pin "15") (pinfunction "USB0_DM_15") (pintype "passive"))
    )
    (net (code "135") (name "unconnected-(LQ-K60P144SYS-VG-USB0_DP-Pad14)") (class "Default")
      (node (ref "LQ-K60P144SYS-VG") (pin "14") (pinfunction "USB0_DP_14") (pintype "passive"))
    )
    (net (code "136") (name "unconnected-(LQ-K60P144SYS-VG-VREFH-Pad25)") (class "Default")
      (node (ref "LQ-K60P144SYS-VG") (pin "25") (pinfunction "VREFH_25") (pintype "passive"))
    )
    (net (code "137") (name "unconnected-(LQ-K60P144SYS-VG-VREGIN-Pad16)") (class "Default")
      (node (ref "LQ-K60P144SYS-VG") (pin "16") (pinfunction "VREGIN_16") (pintype "passive"))
    )
    (net (code "138") (name "unconnected-(P1-Pad5)") (class "Default")
      (node (ref "P1") (pin "5") (pinfunction "5_5") (pintype "passive+no_connect"))
    )
    (net (code "139") (name "unconnected-(P1-Pad6)") (class "Default")
      (node (ref "P1") (pin "6") (pinfunction "6_6") (pintype "passive+no_connect"))
    )
    (net (code "140") (name "unconnected-(P2-Pad5)") (class "Default")
      (node (ref "P2") (pin "5") (pinfunction "5_5") (pintype "passive+no_connect"))
    )
    (net (code "141") (name "unconnected-(P2-Pad6)") (class "Default")
      (node (ref "P2") (pin "6") (pinfunction "6_6") (pintype "passive+no_connect"))
    )
    (net (code "142") (name "unconnected-(P5-CS-Pad7)") (class "Default")
      (node (ref "P5") (pin "7") (pinfunction "CS_7") (pintype "passive+no_connect"))
    )
    (net (code "143") (name "unconnected-(P6-Pad5)") (class "Default")
      (node (ref "P6") (pin "5") (pinfunction "5_5") (pintype "passive+no_connect"))
    )
    (net (code "144") (name "unconnected-(P6-Pad6)") (class "Default")
      (node (ref "P6") (pin "6") (pinfunction "6_6") (pintype "passive+no_connect"))
    )
    (net (code "145") (name "unconnected-(P9-Pad5)") (class "Default")
      (node (ref "P9") (pin "5") (pinfunction "5_5") (pintype "passive+no_connect"))
    )
    (net (code "146") (name "unconnected-(P9-Pad6)") (class "Default")
      (node (ref "P9") (pin "6") (pinfunction "6_6") (pintype "passive+no_connect"))
    )
    (net (code "147") (name "unconnected-(R5-A-Pad1)") (class "Default")
      (node (ref "R5") (pin "1") (pinfunction "A_1") (pintype "passive"))
    )
    (net (code "148") (name "unconnected-(RP1-Pad3)") (class "Default")
      (node (ref "RP1") (pin "3") (pinfunction "3_3") (pintype "passive+no_connect"))
    )
    (net (code "149") (name "unconnected-(RP1-Pad4)") (class "Default")
      (node (ref "RP1") (pin "4") (pinfunction "4_4") (pintype "passive+no_connect"))
    )
    (net (code "150") (name "unconnected-(RP2-Pad3)") (class "Default")
      (node (ref "RP2") (pin "3") (pinfunction "3_3") (pintype "passive"))
    )
    (net (code "151") (name "unconnected-(S2-Pad3)") (class "Default")
      (node (ref "S2") (pin "3") (pinfunction "3_3") (pintype "passive"))
    )
  )
)
